# PROC051C_DUT_Reference.net
KiCad netlist of a schematic drawn in Altium Designer
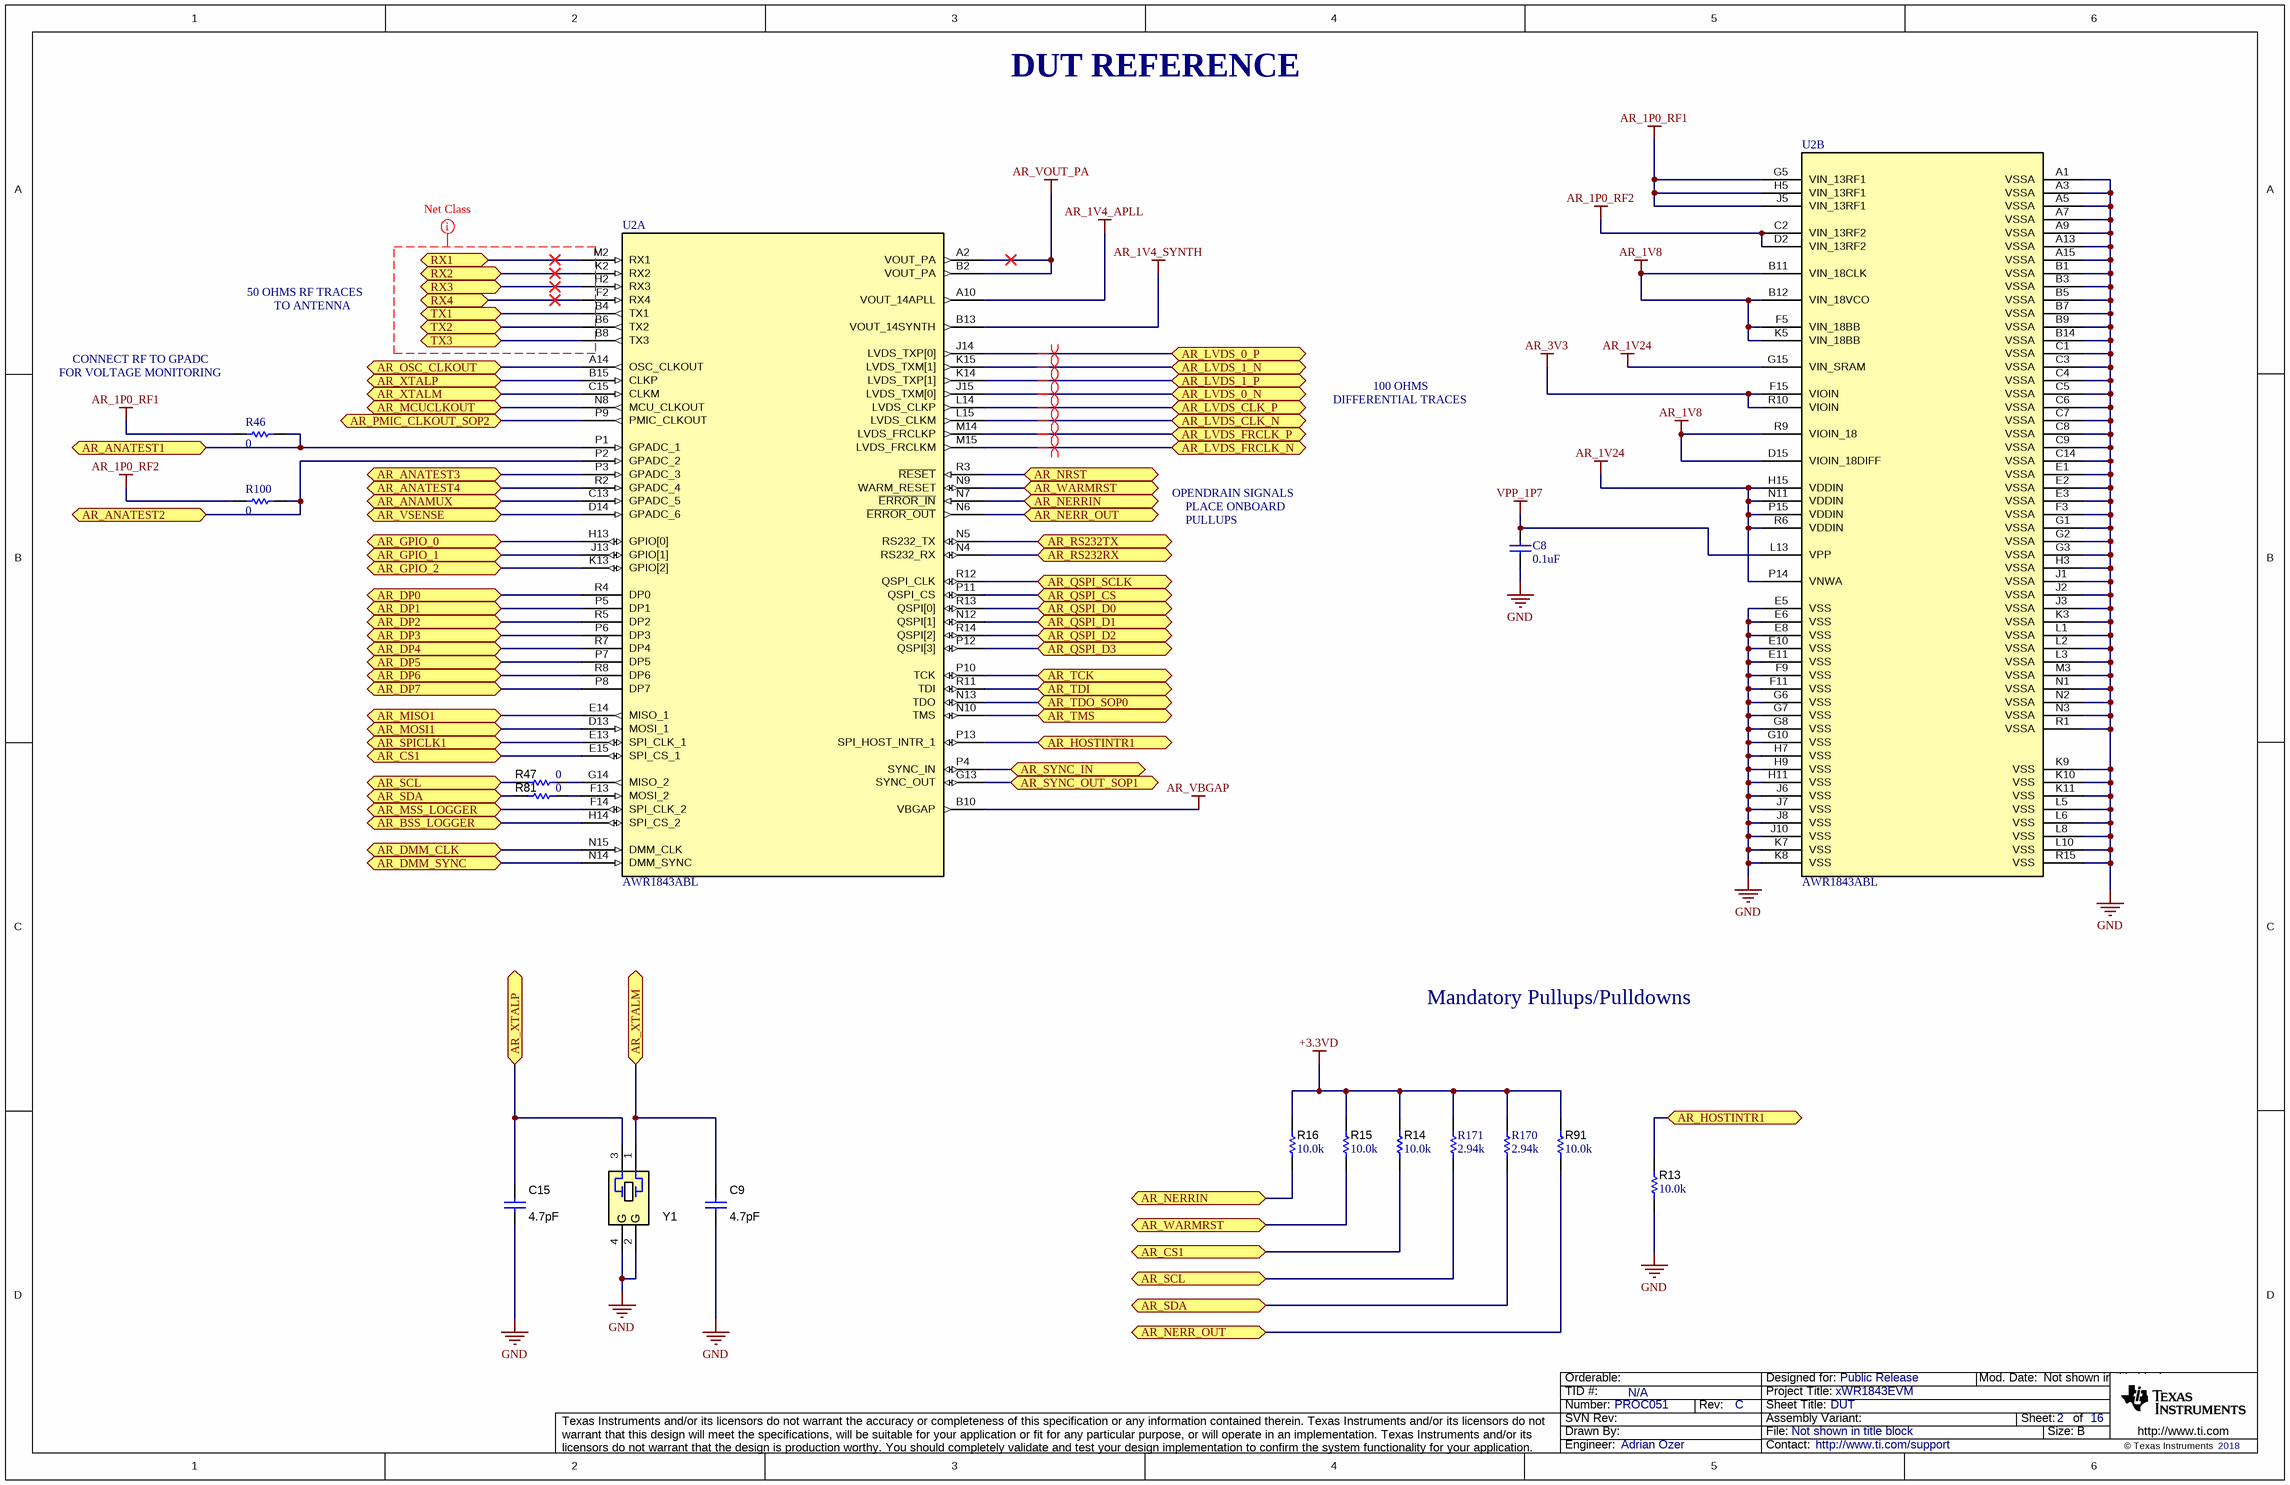
[diagram p0: PROC051C_DUT_Reference.SchDoc]

(export (version "E")
  (design (tool "Eeschema 10.0.6"))
  (components
    (comp (ref "C8")
      (value "GRM033C71A104KE14D")
      (footprint "0201")
      (description "CAP, CERM, 0.1 uF, 10 V,+/- 10%, X7S, 0201")
      (fields
        (field (name "MANUFACTURER") "MuRata")
        (field (name "VALUEDISPLAYED") "0.1uF")
        (field (name "PUBLISHER") "Texas Instruments")
      )
      (libsource (lib "Altium Vault - TI") (part "CMP-0064969-1"))
    )
    (comp (ref "C9")
      (value "GJM1555C1H4R7BB01D")
      (footprint "0402L")
      (description "CAP, CERM, 4.7 pF, 50 V, +/- 2%, C0G/NP0, 0402")
      (fields
        (field (name "MANUFACTURER") "MuRata")
        (field (name "VALUEDISPLAYED") "4.7pF")
        (field (name "PUBLISHER") "Texas Instruments")
      )
      (libsource (lib "Altium Vault - TI") (part "CMP-0006367-2"))
    )
    (comp (ref "C15")
      (value "GJM1555C1H4R7BB01D")
      (footprint "0402L")
      (description "CAP, CERM, 4.7 pF, 50 V, +/- 2%, C0G/NP0, 0402")
      (fields
        (field (name "MANUFACTURER") "MuRata")
        (field (name "VALUEDISPLAYED") "4.7pF")
        (field (name "PUBLISHER") "Texas Instruments")
      )
      (libsource (lib "Altium Vault - TI") (part "CMP-0006367-2"))
    )
    (comp (ref "R13")
      (value "CRCW040210K0FKED")
      (footprint "0402L")
      (description "RES, 10.0 k, 1%, 0.063 W, AEC-Q200 Grade 0, 0402")
      (fields (field (name "MANUFACTURER") "Vishay-Dale") (field (name "VALUEDISPLAYED") "10.0k"))
      (libsource (lib "Altium Vault - TI") (part "Resistor"))
    )
    (comp (ref "R14")
      (value "CRCW040210K0FKED")
      (footprint "0402L")
      (description "RES, 10.0 k, 1%, 0.063 W, AEC-Q200 Grade 0, 0402")
      (fields (field (name "MANUFACTURER") "Vishay-Dale") (field (name "VALUEDISPLAYED") "10.0k"))
      (libsource (lib "Altium Vault - TI") (part "Resistor"))
    )
    (comp (ref "R15")
      (value "CRCW040210K0FKED")
      (footprint "0402L")
      (description "RES, 10.0 k, 1%, 0.063 W, AEC-Q200 Grade 0, 0402")
      (fields (field (name "MANUFACTURER") "Vishay-Dale") (field (name "VALUEDISPLAYED") "10.0k"))
      (libsource (lib "Altium Vault - TI") (part "Resistor"))
    )
    (comp (ref "R16")
      (value "CRCW040210K0FKED")
      (footprint "0402L")
      (description "RES, 10.0 k, 1%, 0.063 W, AEC-Q200 Grade 0, 0402")
      (fields (field (name "MANUFACTURER") "Vishay-Dale") (field (name "VALUEDISPLAYED") "10.0k"))
      (libsource (lib "Altium Vault - TI") (part "Resistor"))
    )
    (comp (ref "R46")
      (value "CRCW04020000Z0ED")
      (footprint "0402")
      (description "RES, 0, 5%, 0.063 W, AEC-Q200 Grade 0, 0402")
      (fields (field (name "MANUFACTURER") "Vishay-Dale") (field (name "VALUEDISPLAYED") "0"))
      (libsource (lib "Altium Vault - TI") (part "CMP-0026822-3"))
    )
    (comp (ref "R47")
      (value "0")
      (footprint "0402L")
      (description "RES, 0, 5%, 0.063 W, AEC-Q200 Grade 0, 0402")
      (fields (field (name "PARTNUMBER") "CRCW04020000Z0ED") (field (name "MANUFACTURER") "Vishay-Dale"))
      (libsource (lib "Altium Vault - TI") (part "Resistor"))
    )
    (comp (ref "R81")
      (value "0")
      (footprint "0402L")
      (description "RES, 0, 5%, 0.063 W, AEC-Q200 Grade 0, 0402")
      (fields (field (name "PARTNUMBER") "CRCW04020000Z0ED") (field (name "MANUFACTURER") "Vishay-Dale"))
      (libsource (lib "Altium Vault - TI") (part "Resistor"))
    )
    (comp (ref "R91")
      (value "CRCW040210K0FKED")
      (footprint "0402L")
      (description "RES, 10.0 k, 1%, 0.063 W, AEC-Q200 Grade 0, 0402")
      (fields (field (name "MANUFACTURER") "Vishay-Dale") (field (name "VALUEDISPLAYED") "10.0k"))
      (libsource (lib "Altium Vault - TI") (part "Resistor"))
    )
    (comp (ref "R100")
      (value "CRCW04020000Z0ED")
      (footprint "0402")
      (description "RES, 0, 5%, 0.063 W, AEC-Q200 Grade 0, 0402")
      (fields (field (name "MANUFACTURER") "Vishay-Dale") (field (name "VALUEDISPLAYED") "0"))
      (libsource (lib "Altium Vault - TI") (part "CMP-0026822-3"))
    )
    (comp (ref "R170")
      (value "CRCW04022K94FKED")
      (footprint "0402")
      (description "RES, 2.94 k, 1%, 0.063 W, AEC-Q200 Grade 0, 0402")
      (fields (field (name "MANUFACTURER") "Vishay-Dale") (field (name "VALUEDISPLAYED") "2.94k"))
      (libsource (lib "Altium Vault - TI") (part "Resistor"))
    )
    (comp (ref "R171")
      (value "CRCW04022K94FKED")
      (footprint "0402")
      (description "RES, 2.94 k, 1%, 0.063 W, AEC-Q200 Grade 0, 0402")
      (fields (field (name "MANUFACTURER") "Vishay-Dale") (field (name "VALUEDISPLAYED") "2.94k"))
      (libsource (lib "Altium Vault - TI") (part "Resistor"))
    )
    (comp (ref "U2")
      (value "AWR1843ABL")
      (footprint "ABL0161B")
      (description "AWR1843ABL, ABL0161B (FCBGA-161)")
      (fields (field (name "PARTNUMBER") "AWR1843ABL") (field (name "MANUFACTURER") "Texas Instruments"))
      (libsource (lib "Altium Vault - TI") (part "AWR1843"))
    )
    (comp (ref "Y1")
      (value "CX3225SA40000D0PTWCC")
      (footprint "Kyocera_CX3225SA")
      (description "Crystal, 40 MHz, 8pF, SMD")
      (fields (field (name "MANUFACTURER") "Kyocera"))
      (libsource (lib "Altium Vault - TI") (part "CMP-0004694-3"))
    )
  )
  (nets
    (net (code "1") (name "+3.3VD") (class "Default")
      (node (ref "R14") (pin "2") (pinfunction "2_2") (pintype "passive"))
      (node (ref "R15") (pin "2") (pinfunction "2_2") (pintype "passive"))
      (node (ref "R16") (pin "2") (pinfunction "2_2") (pintype "passive"))
      (node (ref "R170") (pin "2") (pinfunction "2_2") (pintype "passive"))
      (node (ref "R171") (pin "2") (pinfunction "2_2") (pintype "passive"))
      (node (ref "R91") (pin "2") (pinfunction "2_2") (pintype "passive"))
    )
    (net (code "2") (name "/AR_ANAMUX") (class "Default")
      (node (ref "U2") (pin "C13") (pinfunction "GPADC_5_C13") (pintype "input"))
    )
    (net (code "3") (name "/AR_ANATEST1") (class "Default")
      (node (ref "R46") (pin "1") (pinfunction "1_1") (pintype "passive"))
      (node (ref "U2") (pin "P1") (pinfunction "GPADC_1_P1") (pintype "input"))
    )
    (net (code "4") (name "/AR_ANATEST2") (class "Default")
      (node (ref "R100") (pin "1") (pinfunction "1_1") (pintype "passive"))
      (node (ref "U2") (pin "P2") (pinfunction "GPADC_2_P2") (pintype "input"))
    )
    (net (code "5") (name "/AR_ANATEST3") (class "Default")
      (node (ref "U2") (pin "P3") (pinfunction "GPADC_3_P3") (pintype "input"))
    )
    (net (code "6") (name "/AR_ANATEST4") (class "Default")
      (node (ref "U2") (pin "R2") (pinfunction "GPADC_4_R2") (pintype "input"))
    )
    (net (code "7") (name "/AR_BSS_LOGGER") (class "Default")
      (node (ref "U2") (pin "H14") (pinfunction "SPI_CS_2_H14") (pintype "bidirectional"))
    )
    (net (code "8") (name "/AR_CS1") (class "Default")
      (node (ref "R14") (pin "1") (pinfunction "1_1") (pintype "passive"))
      (node (ref "U2") (pin "E15") (pinfunction "SPI_CS_1_E15") (pintype "bidirectional"))
    )
    (net (code "9") (name "/AR_DMM_CLK") (class "Default")
      (node (ref "U2") (pin "N15") (pinfunction "DMM_CLK_N15") (pintype "input"))
    )
    (net (code "10") (name "/AR_DMM_SYNC") (class "Default")
      (node (ref "U2") (pin "N14") (pinfunction "DMM_SYNC_N14") (pintype "input"))
    )
    (net (code "11") (name "/AR_DP0") (class "Default")
      (node (ref "U2") (pin "R4") (pinfunction "DP0_R4") (pintype "passive"))
    )
    (net (code "12") (name "/AR_DP1") (class "Default")
      (node (ref "U2") (pin "P5") (pinfunction "DP1_P5") (pintype "passive"))
    )
    (net (code "13") (name "/AR_DP2") (class "Default")
      (node (ref "U2") (pin "R5") (pinfunction "DP2_R5") (pintype "passive"))
    )
    (net (code "14") (name "/AR_DP3") (class "Default")
      (node (ref "U2") (pin "P6") (pinfunction "DP3_P6") (pintype "passive"))
    )
    (net (code "15") (name "/AR_DP4") (class "Default")
      (node (ref "U2") (pin "R7") (pinfunction "DP4_R7") (pintype "passive"))
    )
    (net (code "16") (name "/AR_DP5") (class "Default")
      (node (ref "U2") (pin "P7") (pinfunction "DP5_P7") (pintype "passive"))
    )
    (net (code "17") (name "/AR_DP6") (class "Default")
      (node (ref "U2") (pin "R8") (pinfunction "DP6_R8") (pintype "passive"))
    )
    (net (code "18") (name "/AR_DP7") (class "Default")
      (node (ref "U2") (pin "P8") (pinfunction "DP7_P8") (pintype "passive"))
    )
    (net (code "19") (name "/AR_GPIO_0") (class "Default")
      (node (ref "U2") (pin "H13") (pinfunction "GPIO[0]_H13") (pintype "bidirectional"))
    )
    (net (code "20") (name "/AR_GPIO_1") (class "Default")
      (node (ref "U2") (pin "J13") (pinfunction "GPIO[1]_J13") (pintype "bidirectional"))
    )
    (net (code "21") (name "/AR_GPIO_2") (class "Default")
      (node (ref "U2") (pin "K13") (pinfunction "GPIO[2]_K13") (pintype "bidirectional"))
    )
    (net (code "22") (name "/AR_HOSTINTR1") (class "Default")
      (node (ref "R13") (pin "2") (pinfunction "2_2") (pintype "passive"))
      (node (ref "U2") (pin "P13") (pinfunction "SPI_HOST_INTR_1_P13") (pintype "bidirectional"))
    )
    (net (code "23") (name "/AR_LVDS_0_N") (class "Default")
      (node (ref "U2") (pin "J15") (pinfunction "LVDS_TXM[0]_J15") (pintype "output"))
    )
    (net (code "24") (name "/AR_LVDS_0_P") (class "Default")
      (node (ref "U2") (pin "J14") (pinfunction "LVDS_TXP[0]_J14") (pintype "output"))
    )
    (net (code "25") (name "/AR_LVDS_1_N") (class "Default")
      (node (ref "U2") (pin "K15") (pinfunction "LVDS_TXM[1]_K15") (pintype "output"))
    )
    (net (code "26") (name "/AR_LVDS_1_P") (class "Default")
      (node (ref "U2") (pin "K14") (pinfunction "LVDS_TXP[1]_K14") (pintype "output"))
    )
    (net (code "27") (name "/AR_LVDS_CLK_N") (class "Default")
      (node (ref "U2") (pin "L15") (pinfunction "LVDS_CLKM_L15") (pintype "output"))
    )
    (net (code "28") (name "/AR_LVDS_CLK_P") (class "Default")
      (node (ref "U2") (pin "L14") (pinfunction "LVDS_CLKP_L14") (pintype "output"))
    )
    (net (code "29") (name "/AR_LVDS_FRCLK_N") (class "Default")
      (node (ref "U2") (pin "M15") (pinfunction "LVDS_FRCLKM_M15") (pintype "output"))
    )
    (net (code "30") (name "/AR_LVDS_FRCLK_P") (class "Default")
      (node (ref "U2") (pin "M14") (pinfunction "LVDS_FRCLKP_M14") (pintype "output"))
    )
    (net (code "31") (name "/AR_MCUCLKOUT") (class "Default")
      (node (ref "U2") (pin "N8") (pinfunction "MCU_CLKOUT_N8") (pintype "output"))
    )
    (net (code "32") (name "/AR_MISO1") (class "Default")
      (node (ref "U2") (pin "E14") (pinfunction "MISO_1_E14") (pintype "output"))
    )
    (net (code "33") (name "/AR_MOSI1") (class "Default")
      (node (ref "U2") (pin "D13") (pinfunction "MOSI_1_D13") (pintype "input"))
    )
    (net (code "34") (name "/AR_MSS_LOGGER") (class "Default")
      (node (ref "U2") (pin "F14") (pinfunction "SPI_CLK_2_F14") (pintype "bidirectional"))
    )
    (net (code "35") (name "/AR_NERRIN") (class "Default")
      (node (ref "R16") (pin "1") (pinfunction "1_1") (pintype "passive"))
      (node (ref "U2") (pin "N7") (pinfunction "ERROR_IN_N7") (pintype "input"))
    )
    (net (code "36") (name "/AR_NERR_OUT") (class "Default")
      (node (ref "R91") (pin "1") (pinfunction "1_1") (pintype "passive"))
      (node (ref "U2") (pin "N6") (pinfunction "ERROR_OUT_N6") (pintype "output"))
    )
    (net (code "37") (name "/AR_NRST") (class "Default")
      (node (ref "U2") (pin "R3") (pinfunction "RESET_R3") (pintype "input"))
    )
    (net (code "38") (name "/AR_OSC_CLKOUT") (class "Default")
      (node (ref "U2") (pin "A14") (pinfunction "OSC_CLKOUT_A14") (pintype "output"))
    )
    (net (code "39") (name "/AR_PMIC_CLKOUT_SOP2") (class "Default")
      (node (ref "U2") (pin "P9") (pinfunction "PMIC_CLKOUT_P9") (pintype "output"))
    )
    (net (code "40") (name "/AR_QSPI_CS") (class "Default")
      (node (ref "U2") (pin "P11") (pinfunction "QSPI_CS_P11") (pintype "bidirectional"))
    )
    (net (code "41") (name "/AR_QSPI_D0") (class "Default")
      (node (ref "U2") (pin "R13") (pinfunction "QSPI[0]_R13") (pintype "bidirectional"))
    )
    (net (code "42") (name "/AR_QSPI_D1") (class "Default")
      (node (ref "U2") (pin "N12") (pinfunction "QSPI[1]_N12") (pintype "bidirectional"))
    )
    (net (code "43") (name "/AR_QSPI_D2") (class "Default")
      (node (ref "U2") (pin "R14") (pinfunction "QSPI[2]_R14") (pintype "bidirectional"))
    )
    (net (code "44") (name "/AR_QSPI_D3") (class "Default")
      (node (ref "U2") (pin "P12") (pinfunction "QSPI[3]_P12") (pintype "bidirectional"))
    )
    (net (code "45") (name "/AR_QSPI_SCLK") (class "Default")
      (node (ref "U2") (pin "R12") (pinfunction "QSPI_CLK_R12") (pintype "bidirectional"))
    )
    (net (code "46") (name "/AR_RS232RX") (class "Default")
      (node (ref "U2") (pin "N4") (pinfunction "RS232_RX_N4") (pintype "bidirectional"))
    )
    (net (code "47") (name "/AR_RS232TX") (class "Default")
      (node (ref "U2") (pin "N5") (pinfunction "RS232_TX_N5") (pintype "bidirectional"))
    )
    (net (code "48") (name "/AR_SCL") (class "Default")
      (node (ref "R171") (pin "1") (pinfunction "1_1") (pintype "passive"))
      (node (ref "R47") (pin "2") (pinfunction "2_2") (pintype "passive"))
    )
    (net (code "49") (name "/AR_SDA") (class "Default")
      (node (ref "R170") (pin "1") (pinfunction "1_1") (pintype "passive"))
      (node (ref "R81") (pin "2") (pinfunction "2_2") (pintype "passive"))
    )
    (net (code "50") (name "/AR_SPICLK1") (class "Default")
      (node (ref "U2") (pin "E13") (pinfunction "SPI_CLK_1_E13") (pintype "bidirectional"))
    )
    (net (code "51") (name "/AR_SYNC_IN") (class "Default")
      (node (ref "U2") (pin "P4") (pinfunction "SYNC_IN_P4") (pintype "bidirectional"))
    )
    (net (code "52") (name "/AR_SYNC_OUT_SOP1") (class "Default")
      (node (ref "U2") (pin "G13") (pinfunction "SYNC_OUT_G13") (pintype "bidirectional"))
    )
    (net (code "53") (name "/AR_TCK") (class "Default")
      (node (ref "U2") (pin "P10") (pinfunction "TCK_P10") (pintype "bidirectional"))
    )
    (net (code "54") (name "/AR_TDI") (class "Default")
      (node (ref "U2") (pin "R11") (pinfunction "TDI_R11") (pintype "bidirectional"))
    )
    (net (code "55") (name "/AR_TDO_SOP0") (class "Default")
      (node (ref "U2") (pin "N13") (pinfunction "TDO_N13") (pintype "bidirectional"))
    )
    (net (code "56") (name "/AR_TMS") (class "Default")
      (node (ref "U2") (pin "N10") (pinfunction "TMS_N10") (pintype "bidirectional"))
    )
    (net (code "57") (name "/AR_VSENSE") (class "Default")
      (node (ref "U2") (pin "D14") (pinfunction "GPADC_6_D14") (pintype "input"))
    )
    (net (code "58") (name "/AR_WARMRST") (class "Default")
      (node (ref "R15") (pin "1") (pinfunction "1_1") (pintype "passive"))
      (node (ref "U2") (pin "N9") (pinfunction "WARM_RESET_N9") (pintype "bidirectional"))
    )
    (net (code "59") (name "/AR_XTALM") (class "Default")
      (node (ref "C9") (pin "2") (pinfunction "2_2") (pintype "passive"))
      (node (ref "U2") (pin "C15") (pinfunction "CLKM_C15") (pintype "input"))
      (node (ref "Y1") (pin "1") (pinfunction "1_1") (pintype "passive"))
    )
    (net (code "60") (name "/AR_XTALP") (class "Default")
      (node (ref "C15") (pin "2") (pinfunction "2_2") (pintype "passive"))
      (node (ref "U2") (pin "B15") (pinfunction "CLKP_B15") (pintype "input"))
      (node (ref "Y1") (pin "3") (pinfunction "3_3") (pintype "passive"))
    )
    (net (code "61") (name "/RX1") (class "Default")
      (node (ref "U2") (pin "M2") (pinfunction "RX1_M2") (pintype "input"))
    )
    (net (code "62") (name "/RX2") (class "Default")
      (node (ref "U2") (pin "K2") (pinfunction "RX2_K2") (pintype "input"))
    )
    (net (code "63") (name "/RX3") (class "Default")
      (node (ref "U2") (pin "H2") (pinfunction "RX3_H2") (pintype "input"))
    )
    (net (code "64") (name "/RX4") (class "Default")
      (node (ref "U2") (pin "F2") (pinfunction "RX4_F2") (pintype "input"))
    )
    (net (code "65") (name "/TX1") (class "Default")
      (node (ref "U2") (pin "B4") (pinfunction "TX1_B4") (pintype "output"))
    )
    (net (code "66") (name "/TX2") (class "Default")
      (node (ref "U2") (pin "B6") (pinfunction "TX2_B6") (pintype "output"))
    )
    (net (code "67") (name "/TX3") (class "Default")
      (node (ref "U2") (pin "B8") (pinfunction "TX3_B8") (pintype "output"))
    )
    (net (code "68") (name "AR_1P0_RF1") (class "Default")
      (node (ref "R46") (pin "2") (pinfunction "2_2") (pintype "passive"))
      (node (ref "U2") (pin "G5") (pinfunction "VIN_13RF1_G5") (pintype "power_in"))
      (node (ref "U2") (pin "H5") (pinfunction "VIN_13RF1_H5") (pintype "power_in"))
      (node (ref "U2") (pin "J5") (pinfunction "VIN_13RF1_J5") (pintype "power_in"))
    )
    (net (code "69") (name "AR_1P0_RF2") (class "Default")
      (node (ref "R100") (pin "2") (pinfunction "2_2") (pintype "passive"))
      (node (ref "U2") (pin "C2") (pinfunction "VIN_13RF2_C2") (pintype "power_in"))
      (node (ref "U2") (pin "D2") (pinfunction "VIN_13RF2_D2") (pintype "power_in"))
    )
    (net (code "70") (name "AR_1V4_APLL") (class "Default")
      (node (ref "U2") (pin "A10") (pinfunction "VOUT_14APLL_A10") (pintype "output"))
    )
    (net (code "71") (name "AR_1V4_SYNTH") (class "Default")
      (node (ref "U2") (pin "B13") (pinfunction "VOUT_14SYNTH_B13") (pintype "output"))
    )
    (net (code "72") (name "AR_1V8") (class "Default")
      (node (ref "U2") (pin "B11") (pinfunction "VIN_18CLK_B11") (pintype "power_in"))
      (node (ref "U2") (pin "B12") (pinfunction "VIN_18VCO_B12") (pintype "power_in"))
      (node (ref "U2") (pin "D15") (pinfunction "VIOIN_18DIFF_D15") (pintype "power_in"))
      (node (ref "U2") (pin "F5") (pinfunction "VIN_18BB_F5") (pintype "power_in"))
      (node (ref "U2") (pin "K5") (pinfunction "VIN_18BB_K5") (pintype "power_in"))
      (node (ref "U2") (pin "R9") (pinfunction "VIOIN_18_R9") (pintype "power_in"))
    )
    (net (code "73") (name "AR_1V24") (class "Default")
      (node (ref "U2") (pin "G15") (pinfunction "VIN_SRAM_G15") (pintype "power_in"))
      (node (ref "U2") (pin "H15") (pinfunction "VDDIN_H15") (pintype "power_in"))
      (node (ref "U2") (pin "N11") (pinfunction "VDDIN_N11") (pintype "power_in"))
      (node (ref "U2") (pin "P14") (pinfunction "VNWA_P14") (pintype "power_in"))
      (node (ref "U2") (pin "P15") (pinfunction "VDDIN_P15") (pintype "power_in"))
      (node (ref "U2") (pin "R6") (pinfunction "VDDIN_R6") (pintype "power_in"))
    )
    (net (code "74") (name "AR_3V3") (class "Default")
      (node (ref "U2") (pin "F15") (pinfunction "VIOIN_F15") (pintype "power_in"))
      (node (ref "U2") (pin "R10") (pinfunction "VIOIN_R10") (pintype "power_in"))
    )
    (net (code "75") (name "AR_VBGAP") (class "Default")
      (node (ref "U2") (pin "B10") (pinfunction "VBGAP_B10") (pintype "output"))
    )
    (net (code "76") (name "AR_VOUT_PA") (class "Default")
      (node (ref "U2") (pin "A2") (pinfunction "VOUT_PA_A2") (pintype "output"))
      (node (ref "U2") (pin "B2") (pinfunction "VOUT_PA_B2") (pintype "output"))
    )
    (net (code "77") (name "GND") (class "Default")
      (node (ref "C15") (pin "1") (pinfunction "1_1") (pintype "passive"))
      (node (ref "C8") (pin "2") (pinfunction "2_2") (pintype "passive"))
      (node (ref "C9") (pin "1") (pinfunction "1_1") (pintype "passive"))
      (node (ref "R13") (pin "1") (pinfunction "1_1") (pintype "passive"))
      (node (ref "U2") (pin "A1") (pinfunction "VSSA_A1") (pintype "power_in"))
      (node (ref "U2") (pin "A13") (pinfunction "VSSA_A13") (pintype "power_in"))
      (node (ref "U2") (pin "A15") (pinfunction "VSSA_A15") (pintype "power_in"))
      (node (ref "U2") (pin "A3") (pinfunction "VSSA_A3") (pintype "power_in"))
      (node (ref "U2") (pin "A5") (pinfunction "VSSA_A5") (pintype "power_in"))
      (node (ref "U2") (pin "A7") (pinfunction "VSSA_A7") (pintype "power_in"))
      (node (ref "U2") (pin "A9") (pinfunction "VSSA_A9") (pintype "power_in"))
      (node (ref "U2") (pin "B1") (pinfunction "VSSA_B1") (pintype "power_in"))
      (node (ref "U2") (pin "B14") (pinfunction "VSSA_B14") (pintype "power_in"))
      (node (ref "U2") (pin "B3") (pinfunction "VSSA_B3") (pintype "power_in"))
      (node (ref "U2") (pin "B5") (pinfunction "VSSA_B5") (pintype "power_in"))
      (node (ref "U2") (pin "B7") (pinfunction "VSSA_B7") (pintype "power_in"))
      (node (ref "U2") (pin "B9") (pinfunction "VSSA_B9") (pintype "power_in"))
      (node (ref "U2") (pin "C1") (pinfunction "VSSA_C1") (pintype "power_in"))
      (node (ref "U2") (pin "C14") (pinfunction "VSSA_C14") (pintype "power_in"))
      (node (ref "U2") (pin "C3") (pinfunction "VSSA_C3") (pintype "power_in"))
      (node (ref "U2") (pin "C4") (pinfunction "VSSA_C4") (pintype "power_in"))
      (node (ref "U2") (pin "C5") (pinfunction "VSSA_C5") (pintype "power_in"))
      (node (ref "U2") (pin "C6") (pinfunction "VSSA_C6") (pintype "power_in"))
      (node (ref "U2") (pin "C7") (pinfunction "VSSA_C7") (pintype "power_in"))
      (node (ref "U2") (pin "C8") (pinfunction "VSSA_C8") (pintype "power_in"))
      (node (ref "U2") (pin "C9") (pinfunction "VSSA_C9") (pintype "power_in"))
      (node (ref "U2") (pin "E1") (pinfunction "VSSA_E1") (pintype "power_in"))
      (node (ref "U2") (pin "E10") (pinfunction "VSS_E10") (pintype "power_in"))
      (node (ref "U2") (pin "E11") (pinfunction "VSS_E11") (pintype "power_in"))
      (node (ref "U2") (pin "E2") (pinfunction "VSSA_E2") (pintype "power_in"))
      (node (ref "U2") (pin "E3") (pinfunction "VSSA_E3") (pintype "power_in"))
      (node (ref "U2") (pin "E5") (pinfunction "VSS_E5") (pintype "power_in"))
      (node (ref "U2") (pin "E6") (pinfunction "VSS_E6") (pintype "power_in"))
      (node (ref "U2") (pin "E8") (pinfunction "VSS_E8") (pintype "power_in"))
      (node (ref "U2") (pin "F11") (pinfunction "VSS_F11") (pintype "power_in"))
      (node (ref "U2") (pin "F3") (pinfunction "VSSA_F3") (pintype "power_in"))
      (node (ref "U2") (pin "F9") (pinfunction "VSS_F9") (pintype "power_in"))
      (node (ref "U2") (pin "G1") (pinfunction "VSSA_G1") (pintype "power_in"))
      (node (ref "U2") (pin "G10") (pinfunction "VSS_G10") (pintype "power_in"))
      (node (ref "U2") (pin "G2") (pinfunction "VSSA_G2") (pintype "power_in"))
      (node (ref "U2") (pin "G3") (pinfunction "VSSA_G3") (pintype "power_in"))
      (node (ref "U2") (pin "G6") (pinfunction "VSS_G6") (pintype "power_in"))
      (node (ref "U2") (pin "G7") (pinfunction "VSS_G7") (pintype "power_in"))
      (node (ref "U2") (pin "G8") (pinfunction "VSS_G8") (pintype "power_in"))
      (node (ref "U2") (pin "H11") (pinfunction "VSS_H11") (pintype "power_in"))
      (node (ref "U2") (pin "H3") (pinfunction "VSSA_H3") (pintype "power_in"))
      (node (ref "U2") (pin "H7") (pinfunction "VSS_H7") (pintype "power_in"))
      (node (ref "U2") (pin "H9") (pinfunction "VSS_H9") (pintype "power_in"))
      (node (ref "U2") (pin "J1") (pinfunction "VSSA_J1") (pintype "power_in"))
      (node (ref "U2") (pin "J10") (pinfunction "VSS_J10") (pintype "power_in"))
      (node (ref "U2") (pin "J2") (pinfunction "VSSA_J2") (pintype "power_in"))
      (node (ref "U2") (pin "J3") (pinfunction "VSSA_J3") (pintype "power_in"))
      (node (ref "U2") (pin "J6") (pinfunction "VSS_J6") (pintype "power_in"))
      (node (ref "U2") (pin "J7") (pinfunction "VSS_J7") (pintype "power_in"))
      (node (ref "U2") (pin "J8") (pinfunction "VSS_J8") (pintype "power_in"))
      (node (ref "U2") (pin "K10") (pinfunction "VSS_K10") (pintype "power_in"))
      (node (ref "U2") (pin "K11") (pinfunction "VSS_K11") (pintype "power_in"))
      (node (ref "U2") (pin "K3") (pinfunction "VSSA_K3") (pintype "power_in"))
      (node (ref "U2") (pin "K7") (pinfunction "VSS_K7") (pintype "power_in"))
      (node (ref "U2") (pin "K8") (pinfunction "VSS_K8") (pintype "power_in"))
      (node (ref "U2") (pin "K9") (pinfunction "VSS_K9") (pintype "power_in"))
      (node (ref "U2") (pin "L1") (pinfunction "VSSA_L1") (pintype "power_in"))
      (node (ref "U2") (pin "L10") (pinfunction "VSS_L10") (pintype "power_in"))
      (node (ref "U2") (pin "L2") (pinfunction "VSSA_L2") (pintype "power_in"))
      (node (ref "U2") (pin "L3") (pinfunction "VSSA_L3") (pintype "power_in"))
      (node (ref "U2") (pin "L5") (pinfunction "VSS_L5") (pintype "power_in"))
      (node (ref "U2") (pin "L6") (pinfunction "VSS_L6") (pintype "power_in"))
      (node (ref "U2") (pin "L8") (pinfunction "VSS_L8") (pintype "power_in"))
      (node (ref "U2") (pin "M3") (pinfunction "VSSA_M3") (pintype "power_in"))
      (node (ref "U2") (pin "N1") (pinfunction "VSSA_N1") (pintype "power_in"))
      (node (ref "U2") (pin "N2") (pinfunction "VSSA_N2") (pintype "power_in"))
      (node (ref "U2") (pin "N3") (pinfunction "VSSA_N3") (pintype "power_in"))
      (node (ref "U2") (pin "R1") (pinfunction "VSSA_R1") (pintype "power_in"))
      (node (ref "U2") (pin "R15") (pinfunction "VSS_R15") (pintype "power_in"))
      (node (ref "Y1") (pin "2") (pinfunction "GND_2") (pintype "power_in"))
      (node (ref "Y1") (pin "4") (pinfunction "GND_4") (pintype "power_in"))
    )
    (net (code "78") (name "Net-(U2A-MISO_2)") (class "Default")
      (node (ref "R47") (pin "1") (pinfunction "1_1") (pintype "passive"))
      (node (ref "U2") (pin "G14") (pinfunction "MISO_2_G14") (pintype "output"))
    )
    (net (code "79") (name "Net-(U2A-MOSI_2)") (class "Default")
      (node (ref "R81") (pin "1") (pinfunction "1_1") (pintype "passive"))
      (node (ref "U2") (pin "F13") (pinfunction "MOSI_2_F13") (pintype "input"))
    )
    (net (code "80") (name "VPP_1P7") (class "Default")
      (node (ref "C8") (pin "1") (pinfunction "1_1") (pintype "passive"))
      (node (ref "U2") (pin "L13") (pinfunction "VPP_L13") (pintype "power_in"))
    )
  )
)
